# MX25U6435F_eval_0.net
KiCad netlist of a schematic drawn in EAGLE
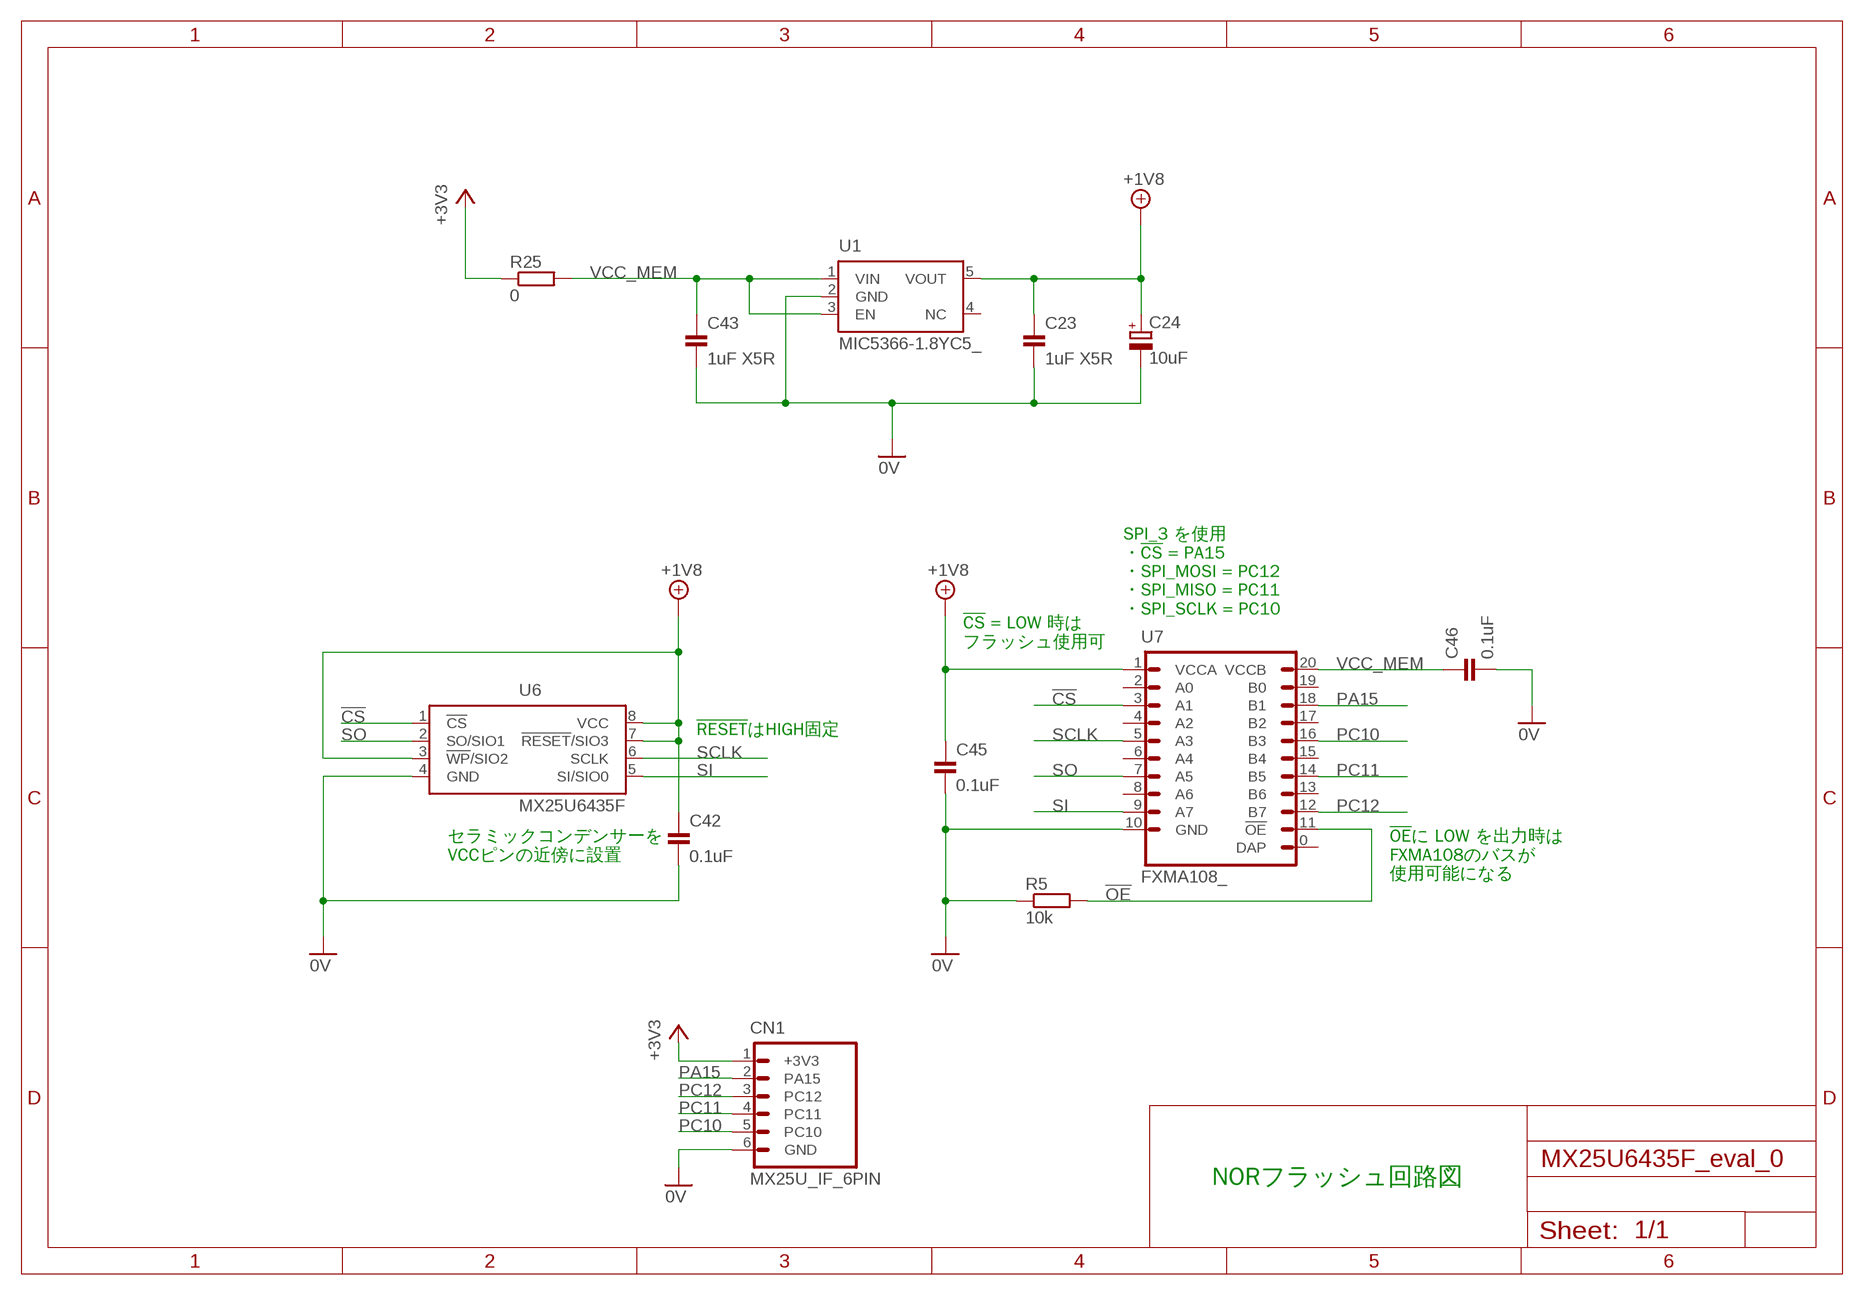
[diagram p0: schematic, sheet 1]

(export (version "E")
  (design (tool "Eeschema 10.0.6"))
  (components
    (comp (ref "C23")
      (value "1uF X5R")
      (footprint "eagle-import:SMD_1608_DEV")
      (libsource (lib "eagle-import") (part "CAP_0603_DEV"))
    )
    (comp (ref "C24")
      (value "10uF")
      (footprint "eagle-import:C1210_TPST_DEV")
      (libsource (lib "eagle-import") (part "TPST106K016R0800_"))
    )
    (comp (ref "C42")
      (value "0.1uF")
      (footprint "eagle-import:SMD_1608_DEV")
      (libsource (lib "eagle-import") (part "CAP_0603_DEV"))
    )
    (comp (ref "C43")
      (value "1uF X5R")
      (footprint "eagle-import:SMD_1608_DEV")
      (libsource (lib "eagle-import") (part "CAP_0603_DEV"))
    )
    (comp (ref "C45")
      (value "0.1uF")
      (footprint "eagle-import:SMD_1608_DEV")
      (libsource (lib "eagle-import") (part "CAP_0603_DEV"))
    )
    (comp (ref "C46")
      (value "0.1uF")
      (footprint "eagle-import:SMD_1608_DEV")
      (libsource (lib "eagle-import") (part "CAP_0603_DEV"))
    )
    (comp (ref "CN1")
      (value "MX25U_IF_6PIN")
      (footprint "eagle-import:HEADER_6PIN")
      (libsource (lib "eagle-import") (part "MX25U_IF_6PIN"))
    )
    (comp (ref "R5")
      (value "10k")
      (footprint "eagle-import:SMD_1608_DEV")
      (libsource (lib "eagle-import") (part "RESISTOR_0603_DEV"))
    )
    (comp (ref "R25")
      (value "0")
      (footprint "eagle-import:SMD_1608_DEV")
      (libsource (lib "eagle-import") (part "RESISTOR_0603_DEV"))
    )
    (comp (ref "U1")
      (value "MIC5366-1.8YC5_")
      (footprint "eagle-import:SC-70-5_DEV")
      (libsource (lib "eagle-import") (part "MIC5366-1.8YC5_"))
    )
    (comp (ref "U6")
      (value "MX25U6435F")
      (footprint "eagle-import:SO8")
      (libsource (lib "eagle-import") (part "MX25U6435F"))
    )
    (comp (ref "U7")
      (value "FXMA108_")
      (footprint "eagle-import:DQFN20_DEV")
      (libsource (lib "eagle-import") (part "FXMA108_"))
    )
  )
  (nets
    (net (code "1") (name "+1V8") (class "Default")
      (node (ref "C23") (pin "1") (pinfunction "1_1") (pintype "passive"))
      (node (ref "C24") (pin "1") (pinfunction "+_1") (pintype "passive"))
      (node (ref "C42") (pin "1") (pinfunction "1_1") (pintype "passive"))
      (node (ref "C45") (pin "1") (pinfunction "1_1") (pintype "passive"))
      (node (ref "U1") (pin "5") (pinfunction "VOUT_5") (pintype "passive"))
      (node (ref "U6") (pin "3") (pinfunction "~{WP}/SIO2_3") (pintype "bidirectional"))
      (node (ref "U6") (pin "7") (pinfunction "~{RESET}/SIO3_7") (pintype "bidirectional"))
      (node (ref "U6") (pin "8") (pinfunction "VCC_8") (pintype "passive"))
      (node (ref "U7") (pin "1") (pinfunction "VCCA_1") (pintype "passive"))
    )
    (net (code "2") (name "+3V3") (class "Default")
      (node (ref "CN1") (pin "1") (pinfunction "+3V3_1") (pintype "passive"))
      (node (ref "R25") (pin "1") (pinfunction "1_1") (pintype "passive"))
    )
    (net (code "3") (name "/PA15") (class "Default")
      (node (ref "CN1") (pin "2") (pinfunction "PA15_2") (pintype "bidirectional"))
      (node (ref "U7") (pin "18") (pinfunction "B1_18") (pintype "bidirectional"))
    )
    (net (code "4") (name "/PC10") (class "Default")
      (node (ref "CN1") (pin "5") (pinfunction "PC10_5") (pintype "bidirectional"))
      (node (ref "U7") (pin "16") (pinfunction "B3_16") (pintype "bidirectional"))
    )
    (net (code "5") (name "/PC11") (class "Default")
      (node (ref "CN1") (pin "4") (pinfunction "PC11_4") (pintype "bidirectional"))
      (node (ref "U7") (pin "14") (pinfunction "B5_14") (pintype "bidirectional"))
    )
    (net (code "6") (name "/PC12") (class "Default")
      (node (ref "CN1") (pin "3") (pinfunction "PC12_3") (pintype "bidirectional"))
      (node (ref "U7") (pin "12") (pinfunction "B7_12") (pintype "bidirectional"))
    )
    (net (code "7") (name "/SCLK") (class "Default")
      (node (ref "U6") (pin "6") (pinfunction "SCLK_6") (pintype "bidirectional"))
      (node (ref "U7") (pin "5") (pinfunction "A3_5") (pintype "bidirectional"))
    )
    (net (code "8") (name "/SI") (class "Default")
      (node (ref "U6") (pin "5") (pinfunction "SI/SIO0_5") (pintype "bidirectional"))
      (node (ref "U7") (pin "9") (pinfunction "A7_9") (pintype "bidirectional"))
    )
    (net (code "9") (name "/SO") (class "Default")
      (node (ref "U6") (pin "2") (pinfunction "SO/SIO1_2") (pintype "bidirectional"))
      (node (ref "U7") (pin "7") (pinfunction "A5_7") (pintype "bidirectional"))
    )
    (net (code "10") (name "/VCC_MEM") (class "Default")
      (node (ref "C43") (pin "1") (pinfunction "1_1") (pintype "passive"))
      (node (ref "C46") (pin "1") (pinfunction "1_1") (pintype "passive"))
      (node (ref "R25") (pin "2") (pinfunction "2_2") (pintype "passive"))
      (node (ref "U1") (pin "1") (pinfunction "VIN_1") (pintype "passive"))
      (node (ref "U1") (pin "3") (pinfunction "EN_3") (pintype "bidirectional"))
      (node (ref "U7") (pin "20") (pinfunction "VCCB_20") (pintype "passive"))
    )
    (net (code "11") (name "/~{CS}") (class "Default")
      (node (ref "U6") (pin "1") (pinfunction "~{CS}_1") (pintype "bidirectional"))
      (node (ref "U7") (pin "3") (pinfunction "A1_3") (pintype "bidirectional"))
    )
    (net (code "12") (name "/~{OE}") (class "Default")
      (node (ref "R5") (pin "2") (pinfunction "2_2") (pintype "passive"))
      (node (ref "U7") (pin "11") (pinfunction "~{OE}_11") (pintype "passive"))
    )
    (net (code "13") (name "0V") (class "Default")
      (node (ref "C23") (pin "2") (pinfunction "2_2") (pintype "passive"))
      (node (ref "C24") (pin "2") (pinfunction "-_2") (pintype "passive"))
      (node (ref "C42") (pin "2") (pinfunction "2_2") (pintype "passive"))
      (node (ref "C43") (pin "2") (pinfunction "2_2") (pintype "passive"))
      (node (ref "C45") (pin "2") (pinfunction "2_2") (pintype "passive"))
      (node (ref "C46") (pin "2") (pinfunction "2_2") (pintype "passive"))
      (node (ref "CN1") (pin "6") (pinfunction "GND_6") (pintype "passive"))
      (node (ref "R5") (pin "1") (pinfunction "1_1") (pintype "passive"))
      (node (ref "U1") (pin "2") (pinfunction "GND_2") (pintype "passive"))
      (node (ref "U6") (pin "4") (pinfunction "GND_4") (pintype "passive"))
      (node (ref "U7") (pin "10") (pinfunction "GND_10") (pintype "passive"))
    )
    (net (code "14") (name "unconnected-(U1-NC-Pad4)") (class "Default")
      (node (ref "U1") (pin "4") (pinfunction "NC_4") (pintype "no_connect"))
    )
    (net (code "15") (name "unconnected-(U7-A0-Pad2)") (class "Default")
      (node (ref "U7") (pin "2") (pinfunction "A0_2") (pintype "bidirectional"))
    )
    (net (code "16") (name "unconnected-(U7-A2-Pad4)") (class "Default")
      (node (ref "U7") (pin "4") (pinfunction "A2_4") (pintype "bidirectional"))
    )
    (net (code "17") (name "unconnected-(U7-A4-Pad6)") (class "Default")
      (node (ref "U7") (pin "6") (pinfunction "A4_6") (pintype "bidirectional"))
    )
    (net (code "18") (name "unconnected-(U7-A6-Pad8)") (class "Default")
      (node (ref "U7") (pin "8") (pinfunction "A6_8") (pintype "bidirectional"))
    )
    (net (code "19") (name "unconnected-(U7-B0-Pad19)") (class "Default")
      (node (ref "U7") (pin "19") (pinfunction "B0_19") (pintype "bidirectional"))
    )
    (net (code "20") (name "unconnected-(U7-B2-Pad17)") (class "Default")
      (node (ref "U7") (pin "17") (pinfunction "B2_17") (pintype "bidirectional"))
    )
    (net (code "21") (name "unconnected-(U7-B4-Pad15)") (class "Default")
      (node (ref "U7") (pin "15") (pinfunction "B4_15") (pintype "bidirectional"))
    )
    (net (code "22") (name "unconnected-(U7-B6-Pad13)") (class "Default")
      (node (ref "U7") (pin "13") (pinfunction "B6_13") (pintype "bidirectional"))
    )
    (net (code "23") (name "unconnected-(U7-DAP-Pad0)") (class "Default")
      (node (ref "U7") (pin "0") (pinfunction "DAP_0") (pintype "no_connect"))
    )
  )
)
